# 09_-_IO.net
KiCad netlist of a schematic drawn in Altium Designer
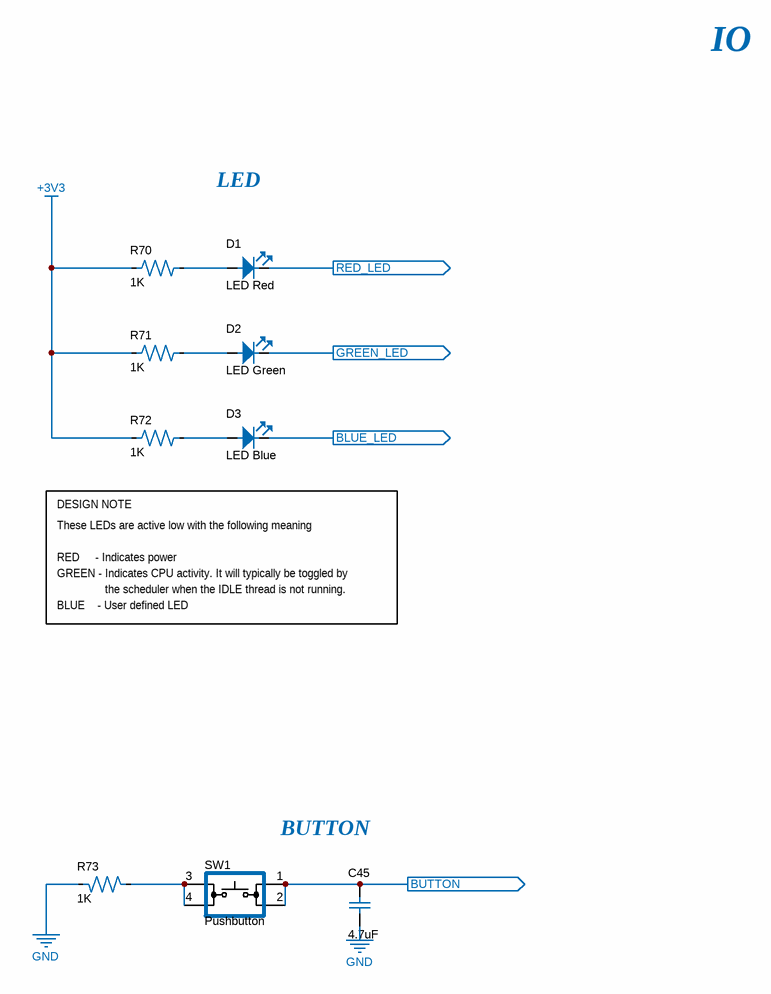
[diagram p0: [09] - IO.SchDoc]

(export (version "E")
  (design (tool "Eeschema 10.0.6"))
  (components
    (comp (ref "C45")
      (value "4.7uF")
      (footprint "C0603")
      (description "C0603")
      (fields (field (name "Comment") "02016D104KAT2A"))
      (libsource (lib "Passive components") (part "02016D104KAT2A"))
    )
    (comp (ref "D1")
      (value "LED Red")
      (footprint "L0603 RED")
      (description "LED 0603 Red")
      (libsource (lib "Diodes") (part "HSMG-C190"))
    )
    (comp (ref "D2")
      (value "LED Green")
      (footprint "L0603 GREEN")
      (description "LED 0603 Green")
      (libsource (lib "Diodes") (part "HSMG-C196"))
    )
    (comp (ref "D3")
      (value "LED Blue")
      (footprint "L0603 BLUE")
      (description "LED 0603 Blue")
      (libsource (lib "Diodes") (part "HSMG-C199"))
    )
    (comp (ref "R70")
      (value "1K")
      (footprint "R0402")
      (description "R0402")
      (fields (field (name "Comment") "CRCW04020000Z0ED"))
      (libsource (lib "Passive components") (part "CRCW04020000Z0ED"))
    )
    (comp (ref "R71")
      (value "1K")
      (footprint "R0402")
      (description "R0402")
      (fields (field (name "Comment") "CRCW04020000Z0ED"))
      (libsource (lib "Passive components") (part "CRCW04020000Z0ED"))
    )
    (comp (ref "R72")
      (value "1K")
      (footprint "R0402")
      (description "R0402")
      (fields (field (name "Comment") "CRCW04020000Z0ED"))
      (libsource (lib "Passive components") (part "CRCW04020000Z0ED"))
    )
    (comp (ref "R73")
      (value "1K")
      (footprint "R0603")
      (description "R0603")
      (fields (field (name "Comment") "CPF-A-0603B100KE1"))
      (libsource (lib "Passive components") (part "CPF-A-0603B100KE1"))
    )
    (comp (ref "SW1")
      (value "Pushbutton")
      (footprint "KSC222G LFS")
      (description "Pushbutton SMD")
      (libsource (lib "Sensors") (part "KSC222G LFS"))
    )
  )
  (nets
    (net (code "1") (name "+3V3") (class "Default")
      (node (ref "R70") (pin "1") (pinfunction "1_1") (pintype "passive"))
      (node (ref "R71") (pin "1") (pinfunction "1_1") (pintype "passive"))
      (node (ref "R72") (pin "1") (pinfunction "1_1") (pintype "passive"))
    )
    (net (code "2") (name "/BLUE_LED") (class "Default")
      (node (ref "D3") (pin "2") (pinfunction "2_2") (pintype "passive"))
    )
    (net (code "3") (name "/BUTTON") (class "Default")
      (node (ref "C45") (pin "2") (pinfunction "2_2") (pintype "passive"))
      (node (ref "SW1") (pin "1") (pinfunction "1_1") (pintype "passive"))
      (node (ref "SW1") (pin "2") (pinfunction "2_2") (pintype "passive"))
    )
    (net (code "4") (name "/GREEN_LED") (class "Default")
      (node (ref "D2") (pin "2") (pinfunction "2_2") (pintype "passive"))
    )
    (net (code "5") (name "/RED_LED") (class "Default")
      (node (ref "D1") (pin "2") (pinfunction "2_2") (pintype "passive"))
    )
    (net (code "6") (name "GND") (class "Default")
      (node (ref "C45") (pin "1") (pinfunction "1_1") (pintype "passive"))
      (node (ref "R73") (pin "2") (pinfunction "2_2") (pintype "passive"))
    )
    (net (code "7") (name "Net-(R70-3)") (class "Default")
      (node (ref "D1") (pin "1") (pinfunction "1_1") (pintype "passive"))
      (node (ref "R70") (pin "2") (pinfunction "3_2") (pintype "passive"))
    )
    (net (code "8") (name "Net-(R71-3)") (class "Default")
      (node (ref "D2") (pin "1") (pinfunction "1_1") (pintype "passive"))
      (node (ref "R71") (pin "2") (pinfunction "3_2") (pintype "passive"))
    )
    (net (code "9") (name "Net-(R72-3)") (class "Default")
      (node (ref "D3") (pin "1") (pinfunction "1_1") (pintype "passive"))
      (node (ref "R72") (pin "2") (pinfunction "3_2") (pintype "passive"))
    )
    (net (code "10") (name "Net-(R73-Pad1)") (class "Default")
      (node (ref "R73") (pin "1") (pinfunction "1_1") (pintype "passive"))
      (node (ref "SW1") (pin "3") (pinfunction "3_3") (pintype "passive"))
      (node (ref "SW1") (pin "4") (pinfunction "4_4") (pintype "passive"))
    )
  )
)
